# Micro_USB.net
KiCad netlist of a schematic drawn in Altium Designer
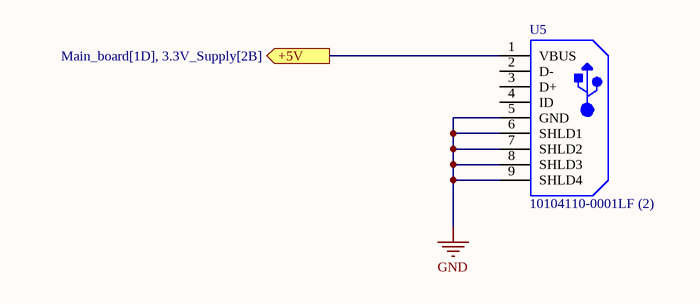
[diagram p0: Micro_USB.SchDoc]

(export (version "E")
  (design (tool "Eeschema 10.0.6"))
  (components
    (comp (ref "U5")
      (value "10104110-0001LF (2)")
      (footprint "FCI-10104110-0001LF_V")
      (description "Usb Connector, 5 Contact(S), Female, Right Angle, Surface Mount Terminal, Locking, Receptacle")
      (fields
        (field (name "MANUFACTURER") "Amphenol Communications Solutions")
        (field (name "MANUFACTURER PART NUMBER") "10104110-0001LF")
      )
      (libsource (lib "ESP32") (part "10104110-0001LF (2)"))
    )
  )
  (nets
    (net (code "1") (name "/+5V") (class "Default")
      (node (ref "U5") (pin "1") (pinfunction "VBUS_1") (pintype "power_in"))
    )
    (net (code "2") (name "GND") (class "Default")
      (node (ref "U5") (pin "5") (pinfunction "GND_5") (pintype "power_in"))
      (node (ref "U5") (pin "6") (pinfunction "SHLD1_6") (pintype "passive"))
      (node (ref "U5") (pin "7") (pinfunction "SHLD2_7") (pintype "passive"))
      (node (ref "U5") (pin "8") (pinfunction "SHLD3_8") (pintype "passive"))
      (node (ref "U5") (pin "9") (pinfunction "SHLD4_9") (pintype "passive"))
    )
    (net (code "3") (name "unconnected-(U5-D+-Pad3)") (class "Default")
      (node (ref "U5") (pin "3") (pinfunction "D+_3") (pintype "passive"))
    )
    (net (code "4") (name "unconnected-(U5-D--Pad2)") (class "Default")
      (node (ref "U5") (pin "2") (pinfunction "D-_2") (pintype "passive"))
    )
    (net (code "5") (name "unconnected-(U5-ID-Pad4)") (class "Default")
      (node (ref "U5") (pin "4") (pinfunction "ID_4") (pintype "passive"))
    )
  )
)
